# Front_left_lamp_v5.net
KiCad netlist of a schematic drawn in EAGLE
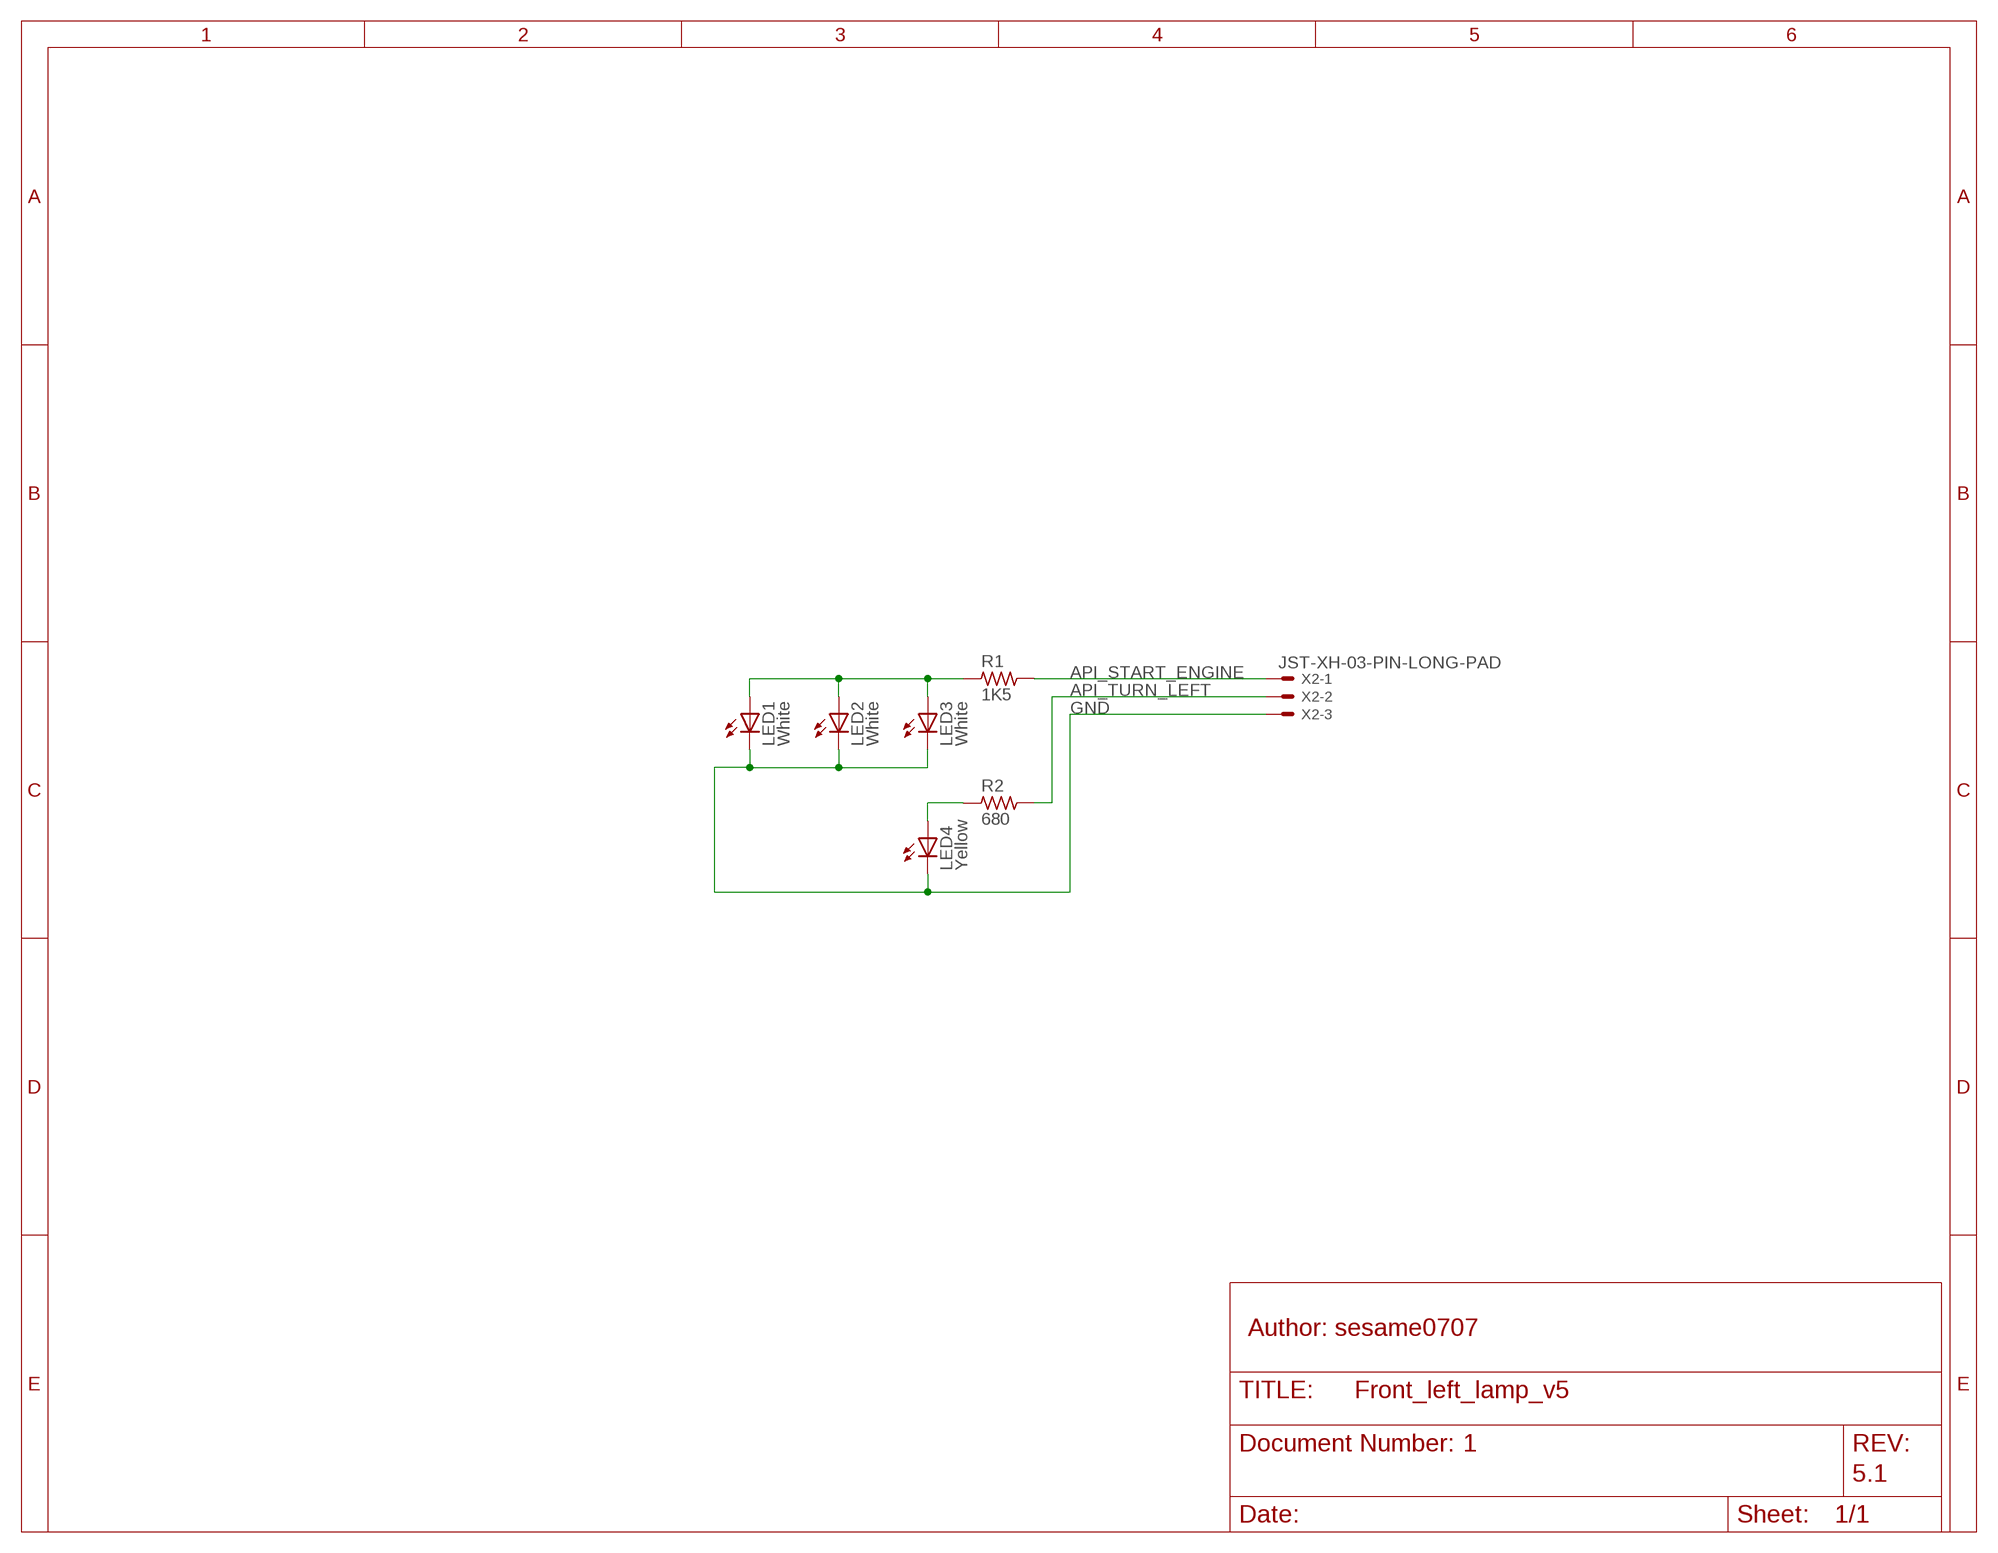
[diagram p0: schematic, sheet 1]

(export (version "E")
  (design (tool "Eeschema 10.0.6"))
  (components
    (comp (ref "LED1")
      (value "White")
      (footprint "eagle-import:LED5MM")
      (fields
        (field (name "MANUFACTURER") "LUCKYLIGHT")
        (field (name "MANUFACTURER_PART_NUMBER") "LL-504WC2V-W2-3PD")
      )
      (libsource (lib "eagle-import") (part "LED5MM"))
    )
    (comp (ref "LED2")
      (value "White")
      (footprint "eagle-import:LED5MM")
      (fields
        (field (name "MANUFACTURER") "LUCKYLIGHT")
        (field (name "MANUFACTURER_PART_NUMBER") "LL-504WC2V-W2-3PD")
      )
      (libsource (lib "eagle-import") (part "LED5MM"))
    )
    (comp (ref "LED3")
      (value "White")
      (footprint "eagle-import:LED5MM")
      (fields
        (field (name "MANUFACTURER") "LUCKYLIGHT")
        (field (name "MANUFACTURER_PART_NUMBER") "LL-504WC2V-W2-3PD")
      )
      (libsource (lib "eagle-import") (part "LED5MM"))
    )
    (comp (ref "LED4")
      (value "Yellow")
      (footprint "eagle-import:LED5MM")
      (fields
        (field (name "MANUFACTURER") "LUCKYLIGHT")
        (field (name "MANUFACTURER_PART_NUMBER") "LL-503YD2E-1B")
      )
      (libsource (lib "eagle-import") (part "LED5MM"))
    )
    (comp (ref "R1")
      (value "1K5")
      (footprint "eagle-import:R1206")
      (fields
        (field (name "MANUFACTURER") "ROYAL OHM")
        (field (name "MANUFACTURER_PART_NUMBER") "1206S4J0152T5E")
      )
      (libsource (lib "eagle-import") (part "R_1206"))
    )
    (comp (ref "R2")
      (value "680")
      (footprint "eagle-import:R1206")
      (fields
        (field (name "MANUFACTURER") "ROYAL OHM")
        (field (name "MANUFACTURER_PART_NUMBER") "1206S4J0681T5E")
      )
      (libsource (lib "eagle-import") (part "R_1206"))
    )
    (comp (ref "X2")
      (value "JST-XH-03-PIN-LONG-PAD")
      (footprint "eagle-import:JST-XH-03-PACKAGE-LONG-PAD")
      (libsource (lib "eagle-import") (part "JST-XH-03-PIN-LONG-PAD"))
    )
  )
  (nets
    (net (code "1") (name "/API_START_ENGINE") (class "Default")
      (node (ref "LED1") (pin "A") (pinfunction "A_A") (pintype "passive"))
      (node (ref "LED2") (pin "A") (pinfunction "A_A") (pintype "passive"))
      (node (ref "LED3") (pin "A") (pinfunction "A_A") (pintype "passive"))
      (node (ref "R1") (pin "1") (pinfunction "1_1") (pintype "passive"))
    )
    (net (code "2") (name "/API_TURN_LEFT") (class "Default")
      (node (ref "R2") (pin "2") (pinfunction "2_2") (pintype "passive"))
      (node (ref "X2") (pin "2") (pinfunction "S_2") (pintype "passive"))
    )
    (net (code "3") (name "/GND") (class "Default")
      (node (ref "LED1") (pin "K") (pinfunction "C_K") (pintype "passive"))
      (node (ref "LED2") (pin "K") (pinfunction "C_K") (pintype "passive"))
      (node (ref "LED3") (pin "K") (pinfunction "C_K") (pintype "passive"))
      (node (ref "LED4") (pin "K") (pinfunction "C_K") (pintype "passive"))
      (node (ref "X2") (pin "3") (pinfunction "S_3") (pintype "passive"))
    )
    (net (code "4") (name "Net-(LED4-PadA)") (class "Default")
      (node (ref "LED4") (pin "A") (pinfunction "A_A") (pintype "passive"))
      (node (ref "R2") (pin "1") (pinfunction "1_1") (pintype "passive"))
    )
    (net (code "5") (name "Net-(X2A-S)") (class "Default")
      (node (ref "R1") (pin "2") (pinfunction "2_2") (pintype "passive"))
      (node (ref "X2") (pin "1") (pinfunction "S_1") (pintype "passive"))
    )
  )
)
